# I2C.net
KiCad netlist of a schematic drawn in Altium Designer
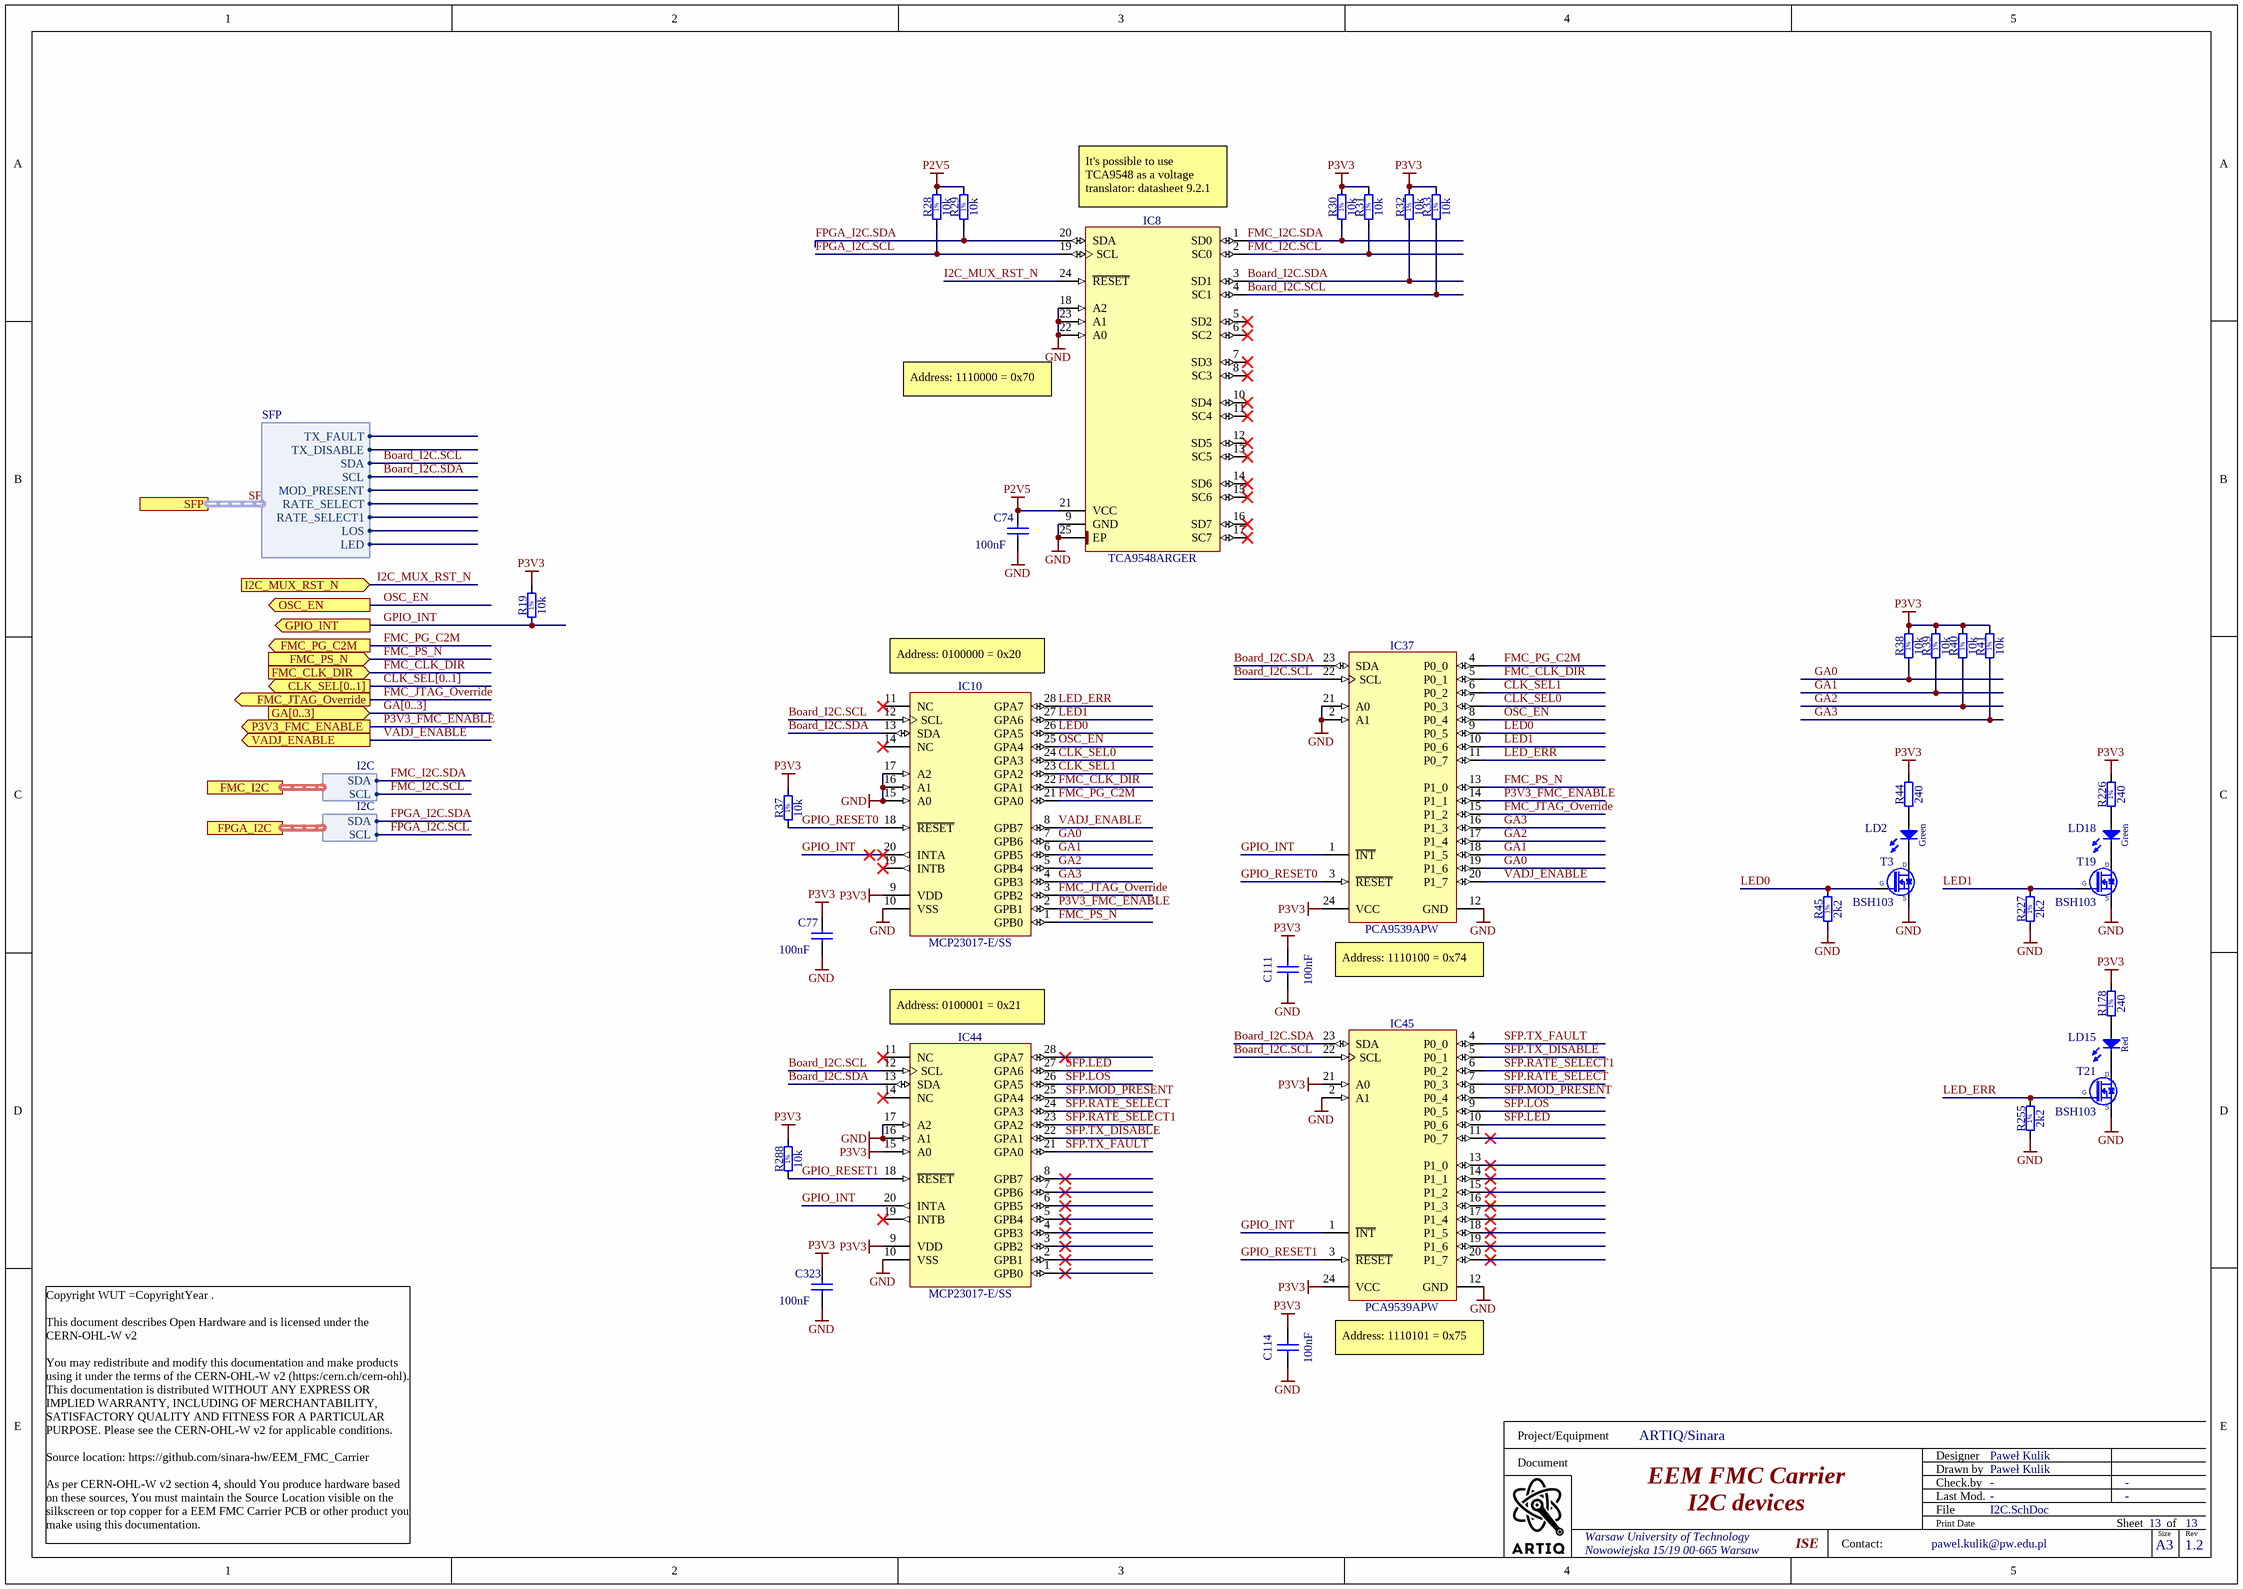
[diagram p0: I2C.SchDoc]

(export (version "E")
  (design (tool "Eeschema 10.0.6"))
  (components
    (comp (ref "C74")
      (value "100nF")
      (footprint "CAPC1005X55N")
      (description "Non-polarised capacitor")
      (fields
        (field (name "PART NUMBER") "CC0402_100NF_16V_10%_X5R")
        (field (name "VOLTAGE") "16V")
        (field (name "AUTHOR") "CERN DEM JLC")
      )
      (libsource (lib "Capacitors") (part "Capacitor - non polarized"))
    )
    (comp (ref "C77")
      (value "100nF")
      (footprint "CAPC1005X55N")
      (description "Non-polarised capacitor")
      (fields
        (field (name "PART NUMBER") "CC0402_100NF_16V_10%_X5R")
        (field (name "VOLTAGE") "16V")
        (field (name "AUTHOR") "CERN DEM JLC")
      )
      (libsource (lib "Capacitors") (part "Capacitor - non polarized"))
    )
    (comp (ref "C111")
      (value "100nF")
      (footprint "CAPC0603X33N")
      (description "Non-polarised capacitor")
      (fields
        (field (name "PART NUMBER") "CC0201_100NF_6.3V_10%_X5R")
        (field (name "VOLTAGE") "6.3V")
        (field (name "AUTHOR") "CERN DEM JLC")
      )
      (libsource (lib "Capacitors") (part "Capacitor - non polarized"))
    )
    (comp (ref "C114")
      (value "100nF")
      (footprint "CAPC0603X33N")
      (description "Non-polarised capacitor")
      (fields
        (field (name "PART NUMBER") "CC0201_100NF_6.3V_10%_X5R")
        (field (name "VOLTAGE") "6.3V")
        (field (name "AUTHOR") "CERN DEM JLC")
      )
      (libsource (lib "Capacitors") (part "Capacitor - non polarized"))
    )
    (comp (ref "C323")
      (value "100nF")
      (footprint "CAPC1005X55N")
      (description "Non-polarised capacitor")
      (fields
        (field (name "PART NUMBER") "CC0402_100NF_16V_10%_X5R")
        (field (name "VOLTAGE") "16V")
        (field (name "AUTHOR") "CERN DEM JLC")
      )
      (libsource (lib "Capacitors") (part "Capacitor - non polarized"))
    )
    (comp (ref "IC8")
      (value "TCA9548ARGER")
      (footprint "QFN50P400X400X100-25N-S220")
      (description "Low Voltage 8-Channel I2C Switch With Reset")
      (fields (field (name "MANUFACTURER") "TEXAS INSTRUMENTS") (field (name "AUTHOR") "CERN DEM JLC"))
      (libsource (lib "ICs And Semiconductors") (part "TCA9548ARGER"))
    )
    (comp (ref "IC10")
      (value "MCP23017-E/SS")
      (footprint "SOP65P780X200-28N")
      (description "16-bit I/O Port Expander With Serial Interface")
      (fields (field (name "MANUFACTURER") "MICROCHIP TECHNOLOGY") (field (name "AUTHOR") "CERN DEM JLC"))
      (libsource (lib "ICs And Semiconductors") (part "MCP23017-E/SS"))
    )
    (comp (ref "IC37")
      (value "PCA9539APW")
      (footprint "SOP65P640X110-24N")
      (description "Low-Voltage 16-Bit I2C-Bus I/O Port with Interrupt and Reset")
      (fields (field (name "MANUFACTURER") "NXP SEMICONDUCTORS") (field (name "AUTHOR") "CERN DEM JMW"))
      (libsource (lib "ICs And Semiconductors") (part "PCA9539APW"))
    )
    (comp (ref "IC44")
      (value "MCP23017-E/SS")
      (footprint "SOP65P780X200-28N")
      (description "16-bit I/O Port Expander With Serial Interface")
      (fields (field (name "MANUFACTURER") "MICROCHIP TECHNOLOGY") (field (name "AUTHOR") "CERN DEM JLC"))
      (libsource (lib "ICs And Semiconductors") (part "MCP23017-E/SS"))
    )
    (comp (ref "IC45")
      (value "PCA9539APW")
      (footprint "SOP65P640X110-24N")
      (description "Low-Voltage 16-Bit I2C-Bus I/O Port with Interrupt and Reset")
      (fields (field (name "MANUFACTURER") "NXP SEMICONDUCTORS") (field (name "AUTHOR") "CERN DEM JMW"))
      (libsource (lib "ICs And Semiconductors") (part "PCA9539APW"))
    )
    (comp (ref "LD2")
      (value "Green")
      (footprint "LED_AVAGO_HSME-C120")
      (description "LED Green 1C 2A")
      (fields
        (field (name "MANUFACTURER PART NUMBER") "HSME-C120")
        (field (name "PART NUMBER") "LED_AVAGO_HSME-C120")
        (field (name "AUTHOR") "CERN DEM JMW")
      )
      (libsource (lib "ICs And Semiconductors") (part "LED Green 1C 2A"))
    )
    (comp (ref "LD15")
      (value "Red")
      (footprint "LED_AVAGO_HSMC-C120")
      (description "LED Red 1C 2A")
      (fields
        (field (name "MANUFACTURER PART NUMBER") "HSMC-C120")
        (field (name "PART NUMBER") "LED_AVAGO_HSMC-C120")
        (field (name "AUTHOR") "CERN DEM JMW")
      )
      (libsource (lib "ICs And Semiconductors") (part "LED Red 1C 2A"))
    )
    (comp (ref "LD18")
      (value "Green")
      (footprint "LED_AVAGO_HSME-C120")
      (description "LED Green 1C 2A")
      (fields
        (field (name "MANUFACTURER PART NUMBER") "HSME-C120")
        (field (name "PART NUMBER") "LED_AVAGO_HSME-C120")
        (field (name "AUTHOR") "CERN DEM JMW")
      )
      (libsource (lib "ICs And Semiconductors") (part "LED Green 1C 2A"))
    )
    (comp (ref "R19")
      (value "10k")
      (footprint "RESC1005X40N")
      (description "Resistor - 1%")
      (fields
        (field (name "PART NUMBER") "R0402_10K_1%_0.0625W_100PPM")
        (field (name "POWER") "0.0625W")
        (field (name "AUTHOR") "CERN DEM JLC")
      )
      (libsource (lib "Resistors") (part "Resistor - 1%"))
    )
    (comp (ref "R28")
      (value "10k")
      (footprint "RESC1005X40N")
      (description "Resistor - 1%")
      (fields
        (field (name "PART NUMBER") "R0402_10K_1%_0.0625W_100PPM")
        (field (name "POWER") "0.0625W")
        (field (name "AUTHOR") "CERN DEM JLC")
      )
      (libsource (lib "Resistors") (part "Resistor - 1%"))
    )
    (comp (ref "R29")
      (value "10k")
      (footprint "RESC1005X40N")
      (description "Resistor - 1%")
      (fields
        (field (name "PART NUMBER") "R0402_10K_1%_0.0625W_100PPM")
        (field (name "POWER") "0.0625W")
        (field (name "AUTHOR") "CERN DEM JLC")
      )
      (libsource (lib "Resistors") (part "Resistor - 1%"))
    )
    (comp (ref "R30")
      (value "10k")
      (footprint "RESC1005X40N")
      (description "Resistor - 1%")
      (fields
        (field (name "PART NUMBER") "R0402_10K_1%_0.0625W_100PPM")
        (field (name "POWER") "0.0625W")
        (field (name "AUTHOR") "CERN DEM JLC")
      )
      (libsource (lib "Resistors") (part "Resistor - 1%"))
    )
    (comp (ref "R31")
      (value "10k")
      (footprint "RESC1005X40N")
      (description "Resistor - 1%")
      (fields
        (field (name "PART NUMBER") "R0402_10K_1%_0.0625W_100PPM")
        (field (name "POWER") "0.0625W")
        (field (name "AUTHOR") "CERN DEM JLC")
      )
      (libsource (lib "Resistors") (part "Resistor - 1%"))
    )
    (comp (ref "R32")
      (value "10k")
      (footprint "RESC1005X40N")
      (description "Resistor - 1%")
      (fields
        (field (name "PART NUMBER") "R0402_10K_1%_0.0625W_100PPM")
        (field (name "POWER") "0.0625W")
        (field (name "AUTHOR") "CERN DEM JLC")
      )
      (libsource (lib "Resistors") (part "Resistor - 1%"))
    )
    (comp (ref "R33")
      (value "10k")
      (footprint "RESC1005X40N")
      (description "Resistor - 1%")
      (fields
        (field (name "PART NUMBER") "R0402_10K_1%_0.0625W_100PPM")
        (field (name "POWER") "0.0625W")
        (field (name "AUTHOR") "CERN DEM JLC")
      )
      (libsource (lib "Resistors") (part "Resistor - 1%"))
    )
    (comp (ref "R37")
      (value "10k")
      (footprint "RESC1005X40N")
      (description "Resistor - 1%")
      (fields
        (field (name "PART NUMBER") "R0402_10K_1%_0.0625W_100PPM")
        (field (name "POWER") "0.0625W")
        (field (name "AUTHOR") "CERN DEM JLC")
      )
      (libsource (lib "Resistors") (part "Resistor - 1%"))
    )
    (comp (ref "R38")
      (value "10k")
      (footprint "RESC1005X40N")
      (description "Resistor - 1%")
      (fields
        (field (name "PART NUMBER") "R0402_10K_1%_0.0625W_100PPM")
        (field (name "POWER") "0.0625W")
        (field (name "AUTHOR") "CERN DEM JLC")
      )
      (libsource (lib "Resistors") (part "Resistor - 1%"))
    )
    (comp (ref "R39")
      (value "10k")
      (footprint "RESC1005X40N")
      (description "Resistor - 1%")
      (fields
        (field (name "PART NUMBER") "R0402_10K_1%_0.0625W_100PPM")
        (field (name "POWER") "0.0625W")
        (field (name "AUTHOR") "CERN DEM JLC")
      )
      (libsource (lib "Resistors") (part "Resistor - 1%"))
    )
    (comp (ref "R40")
      (value "10k")
      (footprint "RESC1005X40N")
      (description "Resistor - 1%")
      (fields
        (field (name "PART NUMBER") "R0402_10K_1%_0.0625W_100PPM")
        (field (name "POWER") "0.0625W")
        (field (name "AUTHOR") "CERN DEM JLC")
      )
      (libsource (lib "Resistors") (part "Resistor - 1%"))
    )
    (comp (ref "R41")
      (value "10k")
      (footprint "RESC1005X40N")
      (description "Resistor - 1%")
      (fields
        (field (name "PART NUMBER") "R0402_10K_1%_0.0625W_100PPM")
        (field (name "POWER") "0.0625W")
        (field (name "AUTHOR") "CERN DEM JLC")
      )
      (libsource (lib "Resistors") (part "Resistor - 1%"))
    )
    (comp (ref "R44")
      (value "240")
      (footprint "RESC1005X40N")
      (description "Resistor - 1%")
      (fields
        (field (name "PART NUMBER") "R0402_240R_1%_0.0625W_100PPM")
        (field (name "POWER") "0.0625W")
        (field (name "AUTHOR") "CERN DEM JLC")
      )
      (libsource (lib "Resistors") (part "Resistor - 1%"))
    )
    (comp (ref "R45")
      (value "2k2")
      (footprint "RESC1005X40N")
      (description "Resistor - 1%")
      (fields
        (field (name "PART NUMBER") "R0402_2K2_1%_0.0625W_100PPM")
        (field (name "POWER") "0.0625W")
        (field (name "AUTHOR") "CERN DEM JLC")
      )
      (libsource (lib "Resistors") (part "Resistor - 1%"))
    )
    (comp (ref "R178")
      (value "240")
      (footprint "RESC1005X40N")
      (description "Resistor - 1%")
      (fields
        (field (name "PART NUMBER") "R0402_240R_1%_0.0625W_100PPM")
        (field (name "POWER") "0.0625W")
        (field (name "AUTHOR") "CERN DEM JLC")
      )
      (libsource (lib "Resistors") (part "Resistor - 1%"))
    )
    (comp (ref "R226")
      (value "240")
      (footprint "RESC1005X40N")
      (description "Resistor - 1%")
      (fields
        (field (name "PART NUMBER") "R0402_240R_1%_0.0625W_100PPM")
        (field (name "POWER") "0.0625W")
        (field (name "AUTHOR") "CERN DEM JLC")
      )
      (libsource (lib "Resistors") (part "Resistor - 1%"))
    )
    (comp (ref "R227")
      (value "2k2")
      (footprint "RESC1005X40N")
      (description "Resistor - 1%")
      (fields
        (field (name "PART NUMBER") "R0402_2K2_1%_0.0625W_100PPM")
        (field (name "POWER") "0.0625W")
        (field (name "AUTHOR") "CERN DEM JLC")
      )
      (libsource (lib "Resistors") (part "Resistor - 1%"))
    )
    (comp (ref "R255")
      (value "2k2")
      (footprint "RESC1005X40N")
      (description "Resistor - 1%")
      (fields
        (field (name "PART NUMBER") "R0402_2K2_1%_0.0625W_100PPM")
        (field (name "POWER") "0.0625W")
        (field (name "AUTHOR") "CERN DEM JLC")
      )
      (libsource (lib "Resistors") (part "Resistor - 1%"))
    )
    (comp (ref "R288")
      (value "10k")
      (footprint "RESC1005X40N")
      (description "Resistor - 1%")
      (fields
        (field (name "PART NUMBER") "R0402_10K_1%_0.0625W_100PPM")
        (field (name "POWER") "0.0625W")
        (field (name "AUTHOR") "CERN DEM JLC")
      )
      (libsource (lib "Resistors") (part "Resistor - 1%"))
    )
    (comp (ref "T3")
      (value "BSH103")
      (footprint "SOT95P230X110-3N")
      (description "N-CHANNEL MOSFET WITH DIODE")
      (fields (field (name "MANUFACTURER") "NEXPERIA") (field (name "AUTHOR") "CERN DEM JLC"))
      (libsource (lib "ICs And Semiconductors") (part "N-MOSFET-D 1G 2S 3D"))
    )
    (comp (ref "T19")
      (value "BSH103")
      (footprint "SOT95P230X110-3N")
      (description "N-CHANNEL MOSFET WITH DIODE")
      (fields (field (name "MANUFACTURER") "NEXPERIA") (field (name "AUTHOR") "CERN DEM JLC"))
      (libsource (lib "ICs And Semiconductors") (part "N-MOSFET-D 1G 2S 3D"))
    )
    (comp (ref "T21")
      (value "BSH103")
      (footprint "SOT95P230X110-3N")
      (description "N-CHANNEL MOSFET WITH DIODE")
      (fields (field (name "MANUFACTURER") "NEXPERIA") (field (name "AUTHOR") "CERN DEM JLC"))
      (libsource (lib "ICs And Semiconductors") (part "N-MOSFET-D 1G 2S 3D"))
    )
  )
  (nets
    (net (code "3") (name "/Board_I2C.SCL") (class "Default")
      (node (ref "IC10") (pin "12") (pinfunction "SCL_12") (pintype "input"))
      (node (ref "IC37") (pin "22") (pinfunction "SCL_22") (pintype "input"))
      (node (ref "IC44") (pin "12") (pinfunction "SCL_12") (pintype "input"))
      (node (ref "IC45") (pin "22") (pinfunction "SCL_22") (pintype "input"))
      (node (ref "IC8") (pin "4") (pinfunction "SC1_4") (pintype "bidirectional"))
      (node (ref "R33") (pin "1") (pinfunction "1_1") (pintype "passive"))
    )
    (net (code "4") (name "/Board_I2C.SDA") (class "Default")
      (node (ref "IC10") (pin "13") (pinfunction "SDA_13") (pintype "bidirectional"))
      (node (ref "IC37") (pin "23") (pinfunction "SDA_23") (pintype "bidirectional"))
      (node (ref "IC44") (pin "13") (pinfunction "SDA_13") (pintype "bidirectional"))
      (node (ref "IC45") (pin "23") (pinfunction "SDA_23") (pintype "bidirectional"))
      (node (ref "IC8") (pin "3") (pinfunction "SD1_3") (pintype "bidirectional"))
      (node (ref "R32") (pin "1") (pinfunction "1_1") (pintype "passive"))
    )
    (net (code "5") (name "/CLK_SEL0") (class "Default")
      (node (ref "IC10") (pin "24") (pinfunction "GPA3_24") (pintype "bidirectional"))
      (node (ref "IC37") (pin "7") (pinfunction "P0_3_7") (pintype "bidirectional"))
    )
    (net (code "6") (name "/CLK_SEL1") (class "Default")
      (node (ref "IC10") (pin "23") (pinfunction "GPA2_23") (pintype "bidirectional"))
      (node (ref "IC37") (pin "6") (pinfunction "P0_2_6") (pintype "bidirectional"))
    )
    (net (code "8") (name "/FMC_CLK_DIR") (class "Default")
      (node (ref "IC10") (pin "22") (pinfunction "GPA1_22") (pintype "bidirectional"))
      (node (ref "IC37") (pin "5") (pinfunction "P0_1_5") (pintype "bidirectional"))
    )
    (net (code "9") (name "/FMC_I2C.SCL") (class "Default")
      (node (ref "IC8") (pin "2") (pinfunction "SC0_2") (pintype "bidirectional"))
      (node (ref "R31") (pin "1") (pinfunction "1_1") (pintype "passive"))
    )
    (net (code "10") (name "/FMC_I2C.SDA") (class "Default")
      (node (ref "IC8") (pin "1") (pinfunction "SD0_1") (pintype "bidirectional"))
      (node (ref "R30") (pin "1") (pinfunction "1_1") (pintype "passive"))
    )
    (net (code "11") (name "/FMC_JTAG_Override") (class "Default")
      (node (ref "IC10") (pin "3") (pinfunction "GPB2_3") (pintype "bidirectional"))
      (node (ref "IC37") (pin "15") (pinfunction "P1_2_15") (pintype "bidirectional"))
    )
    (net (code "12") (name "/FMC_PG_C2M") (class "Default")
      (node (ref "IC10") (pin "21") (pinfunction "GPA0_21") (pintype "bidirectional"))
      (node (ref "IC37") (pin "4") (pinfunction "P0_0_4") (pintype "bidirectional"))
    )
    (net (code "13") (name "/FMC_PS_N") (class "Default")
      (node (ref "IC10") (pin "1") (pinfunction "GPB0_1") (pintype "bidirectional"))
      (node (ref "IC37") (pin "13") (pinfunction "P1_0_13") (pintype "bidirectional"))
    )
    (net (code "14") (name "/FPGA_I2C.SCL") (class "Default")
      (node (ref "IC8") (pin "19") (pinfunction "SCL_19") (pintype "bidirectional"))
      (node (ref "R28") (pin "1") (pinfunction "1_1") (pintype "passive"))
    )
    (net (code "15") (name "/FPGA_I2C.SDA") (class "Default")
      (node (ref "IC8") (pin "20") (pinfunction "SDA_20") (pintype "bidirectional"))
      (node (ref "R29") (pin "1") (pinfunction "1_1") (pintype "passive"))
    )
    (net (code "16") (name "/GA0") (class "Default")
      (node (ref "IC10") (pin "7") (pinfunction "GPB6_7") (pintype "bidirectional"))
      (node (ref "IC37") (pin "19") (pinfunction "P1_6_19") (pintype "bidirectional"))
      (node (ref "R38") (pin "1") (pinfunction "1_1") (pintype "passive"))
    )
    (net (code "17") (name "/GA1") (class "Default")
      (node (ref "IC10") (pin "6") (pinfunction "GPB5_6") (pintype "bidirectional"))
      (node (ref "IC37") (pin "18") (pinfunction "P1_5_18") (pintype "bidirectional"))
      (node (ref "R39") (pin "1") (pinfunction "1_1") (pintype "passive"))
    )
    (net (code "18") (name "/GA2") (class "Default")
      (node (ref "IC10") (pin "5") (pinfunction "GPB4_5") (pintype "bidirectional"))
      (node (ref "IC37") (pin "17") (pinfunction "P1_4_17") (pintype "bidirectional"))
      (node (ref "R40") (pin "1") (pinfunction "1_1") (pintype "passive"))
    )
    (net (code "19") (name "/GA3") (class "Default")
      (node (ref "IC10") (pin "4") (pinfunction "GPB3_4") (pintype "bidirectional"))
      (node (ref "IC37") (pin "16") (pinfunction "P1_3_16") (pintype "bidirectional"))
      (node (ref "R41") (pin "1") (pinfunction "1_1") (pintype "passive"))
    )
    (net (code "21") (name "/GPIO_INT") (class "Default")
      (node (ref "IC10") (pin "20") (pinfunction "INTA_20") (pintype "output"))
      (node (ref "IC37") (pin "1") (pinfunction "~{INT}_1") (pintype "open_collector"))
      (node (ref "IC44") (pin "20") (pinfunction "INTA_20") (pintype "output"))
      (node (ref "IC45") (pin "1") (pinfunction "~{INT}_1") (pintype "open_collector"))
      (node (ref "R19") (pin "1") (pinfunction "1_1") (pintype "passive"))
    )
    (net (code "22") (name "/GPIO_RESET0") (class "Default")
      (node (ref "IC10") (pin "18") (pinfunction "~{RESET}_18") (pintype "input"))
      (node (ref "IC37") (pin "3") (pinfunction "~{RESET}_3") (pintype "input"))
      (node (ref "R37") (pin "1") (pinfunction "1_1") (pintype "passive"))
    )
    (net (code "23") (name "/GPIO_RESET1") (class "Default")
      (node (ref "IC44") (pin "18") (pinfunction "~{RESET}_18") (pintype "input"))
      (node (ref "IC45") (pin "3") (pinfunction "~{RESET}_3") (pintype "input"))
      (node (ref "R288") (pin "1") (pinfunction "1_1") (pintype "passive"))
    )
    (net (code "24") (name "/I2C_MUX_RST_N") (class "Default")
      (node (ref "IC8") (pin "24") (pinfunction "~{RESET}_24") (pintype "input"))
    )
    (net (code "25") (name "/LED0") (class "Default")
      (node (ref "IC10") (pin "26") (pinfunction "GPA5_26") (pintype "bidirectional"))
      (node (ref "IC37") (pin "9") (pinfunction "P0_5_9") (pintype "bidirectional"))
      (node (ref "R45") (pin "2") (pinfunction "2_2") (pintype "passive"))
      (node (ref "T3") (pin "1") (pinfunction "G_1") (pintype "passive"))
    )
    (net (code "26") (name "/LED1") (class "Default")
      (node (ref "IC10") (pin "27") (pinfunction "GPA6_27") (pintype "bidirectional"))
      (node (ref "IC37") (pin "10") (pinfunction "P0_6_10") (pintype "bidirectional"))
      (node (ref "R227") (pin "2") (pinfunction "2_2") (pintype "passive"))
      (node (ref "T19") (pin "1") (pinfunction "G_1") (pintype "passive"))
    )
    (net (code "27") (name "/LED_ERR") (class "Default")
      (node (ref "IC10") (pin "28") (pinfunction "GPA7_28") (pintype "bidirectional"))
      (node (ref "IC37") (pin "11") (pinfunction "P0_7_11") (pintype "bidirectional"))
      (node (ref "R255") (pin "2") (pinfunction "2_2") (pintype "passive"))
      (node (ref "T21") (pin "1") (pinfunction "G_1") (pintype "passive"))
    )
    (net (code "28") (name "/OSC_EN") (class "Default")
      (node (ref "IC10") (pin "25") (pinfunction "GPA4_25") (pintype "bidirectional"))
      (node (ref "IC37") (pin "8") (pinfunction "P0_4_8") (pintype "bidirectional"))
    )
    (net (code "29") (name "/P3V3_FMC_ENABLE") (class "Default")
      (node (ref "IC10") (pin "2") (pinfunction "GPB1_2") (pintype "bidirectional"))
      (node (ref "IC37") (pin "14") (pinfunction "P1_1_14") (pintype "bidirectional"))
    )
    (net (code "30") (name "/SFP.LED") (class "Default")
      (node (ref "IC44") (pin "27") (pinfunction "GPA6_27") (pintype "bidirectional"))
      (node (ref "IC45") (pin "10") (pinfunction "P0_6_10") (pintype "bidirectional"))
    )
    (net (code "31") (name "/SFP.LOS") (class "Default")
      (node (ref "IC44") (pin "26") (pinfunction "GPA5_26") (pintype "bidirectional"))
      (node (ref "IC45") (pin "9") (pinfunction "P0_5_9") (pintype "bidirectional"))
    )
    (net (code "32") (name "/SFP.MOD_PRESENT") (class "Default")
      (node (ref "IC44") (pin "25") (pinfunction "GPA4_25") (pintype "bidirectional"))
      (node (ref "IC45") (pin "8") (pinfunction "P0_4_8") (pintype "bidirectional"))
    )
    (net (code "33") (name "/SFP.RATE_SELECT") (class "Default")
      (node (ref "IC44") (pin "24") (pinfunction "GPA3_24") (pintype "bidirectional"))
      (node (ref "IC45") (pin "7") (pinfunction "P0_3_7") (pintype "bidirectional"))
    )
    (net (code "34") (name "/SFP.RATE_SELECT1") (class "Default")
      (node (ref "IC44") (pin "23") (pinfunction "GPA2_23") (pintype "bidirectional"))
      (node (ref "IC45") (pin "6") (pinfunction "P0_2_6") (pintype "bidirectional"))
    )
    (net (code "35") (name "/SFP.TX_DISABLE") (class "Default")
      (node (ref "IC44") (pin "22") (pinfunction "GPA1_22") (pintype "bidirectional"))
      (node (ref "IC45") (pin "5") (pinfunction "P0_1_5") (pintype "bidirectional"))
    )
    (net (code "36") (name "/SFP.TX_FAULT") (class "Default")
      (node (ref "IC44") (pin "21") (pinfunction "GPA0_21") (pintype "bidirectional"))
      (node (ref "IC45") (pin "4") (pinfunction "P0_0_4") (pintype "bidirectional"))
    )
    (net (code "38") (name "/VADJ_ENABLE") (class "Default")
      (node (ref "IC10") (pin "8") (pinfunction "GPB7_8") (pintype "bidirectional"))
      (node (ref "IC37") (pin "20") (pinfunction "P1_7_20") (pintype "bidirectional"))
    )
    (net (code "40") (name "GND") (class "Default")
      (node (ref "C111") (pin "1") (pinfunction "1_1") (pintype "passive"))
      (node (ref "C114") (pin "1") (pinfunction "1_1") (pintype "passive"))
      (node (ref "C323") (pin "1") (pinfunction "1_1") (pintype "passive"))
      (node (ref "C74") (pin "1") (pinfunction "1_1") (pintype "passive"))
      (node (ref "C77") (pin "1") (pinfunction "1_1") (pintype "passive"))
      (node (ref "IC10") (pin "10") (pinfunction "VSS_10") (pintype "power_in"))
      (node (ref "IC10") (pin "15") (pinfunction "A0_15") (pintype "input"))
      (node (ref "IC10") (pin "16") (pinfunction "A1_16") (pintype "input"))
      (node (ref "IC10") (pin "17") (pinfunction "A2_17") (pintype "input"))
      (node (ref "IC37") (pin "12") (pinfunction "GND_12") (pintype "power_in"))
      (node (ref "IC37") (pin "2") (pinfunction "A1_2") (pintype "input"))
      (node (ref "IC37") (pin "21") (pinfunction "A0_21") (pintype "input"))
      (node (ref "IC44") (pin "10") (pinfunction "VSS_10") (pintype "power_in"))
      (node (ref "IC44") (pin "16") (pinfunction "A1_16") (pintype "input"))
      (node (ref "IC44") (pin "17") (pinfunction "A2_17") (pintype "input"))
      (node (ref "IC45") (pin "12") (pinfunction "GND_12") (pintype "power_in"))
      (node (ref "IC45") (pin "2") (pinfunction "A1_2") (pintype "input"))
      (node (ref "IC8") (pin "18") (pinfunction "A2_18") (pintype "input"))
      (node (ref "IC8") (pin "22") (pinfunction "A0_22") (pintype "input"))
      (node (ref "IC8") (pin "23") (pinfunction "A1_23") (pintype "input"))
      (node (ref "IC8") (pin "25") (pinfunction "EP_25") (pintype "power_in"))
      (node (ref "IC8") (pin "9") (pinfunction "GND_9") (pintype "power_in"))
      (node (ref "R227") (pin "1") (pinfunction "1_1") (pintype "passive"))
      (node (ref "R255") (pin "1") (pinfunction "1_1") (pintype "passive"))
      (node (ref "R45") (pin "1") (pinfunction "1_1") (pintype "passive"))
      (node (ref "T19") (pin "2") (pinfunction "S_2") (pintype "passive"))
      (node (ref "T21") (pin "2") (pinfunction "S_2") (pintype "passive"))
      (node (ref "T3") (pin "2") (pinfunction "S_2") (pintype "passive"))
    )
    (net (code "41") (name "Net-(LD2-A)") (class "Default")
      (node (ref "LD2") (pin "2") (pinfunction "A_2") (pintype "passive"))
      (node (ref "R44") (pin "1") (pinfunction "1_1") (pintype "passive"))
    )
    (net (code "42") (name "Net-(LD2-C)") (class "Default")
      (node (ref "LD2") (pin "1") (pinfunction "C_1") (pintype "passive"))
      (node (ref "T3") (pin "3") (pinfunction "D_3") (pintype "passive"))
    )
    (net (code "43") (name "Net-(LD15-A)") (class "Default")
      (node (ref "LD15") (pin "2") (pinfunction "A_2") (pintype "passive"))
      (node (ref "R178") (pin "1") (pinfunction "1_1") (pintype "passive"))
    )
    (net (code "44") (name "Net-(LD15-C)") (class "Default")
      (node (ref "LD15") (pin "1") (pinfunction "C_1") (pintype "passive"))
      (node (ref "T21") (pin "3") (pinfunction "D_3") (pintype "passive"))
    )
    (net (code "45") (name "Net-(LD18-A)") (class "Default")
      (node (ref "LD18") (pin "2") (pinfunction "A_2") (pintype "passive"))
      (node (ref "R226") (pin "1") (pinfunction "1_1") (pintype "passive"))
    )
    (net (code "46") (name "Net-(LD18-C)") (class "Default")
      (node (ref "LD18") (pin "1") (pinfunction "C_1") (pintype "passive"))
      (node (ref "T19") (pin "3") (pinfunction "D_3") (pintype "passive"))
    )
    (net (code "47") (name "P2V5") (class "Default")
      (node (ref "C74") (pin "2") (pinfunction "2_2") (pintype "passive"))
      (node (ref "IC8") (pin "21") (pinfunction "VCC_21") (pintype "power_in"))
      (node (ref "R28") (pin "2") (pinfunction "2_2") (pintype "passive"))
      (node (ref "R29") (pin "2") (pinfunction "2_2") (pintype "passive"))
    )
    (net (code "48") (name "P3V3") (class "Default")
      (node (ref "C111") (pin "2") (pinfunction "2_2") (pintype "passive"))
      (node (ref "C114") (pin "2") (pinfunction "2_2") (pintype "passive"))
      (node (ref "C323") (pin "2") (pinfunction "2_2") (pintype "passive"))
      (node (ref "C77") (pin "2") (pinfunction "2_2") (pintype "passive"))
      (node (ref "IC10") (pin "9") (pinfunction "VDD_9") (pintype "power_in"))
      (node (ref "IC37") (pin "24") (pinfunction "VCC_24") (pintype "power_in"))
      (node (ref "IC44") (pin "15") (pinfunction "A0_15") (pintype "input"))
      (node (ref "IC44") (pin "9") (pinfunction "VDD_9") (pintype "power_in"))
      (node (ref "IC45") (pin "21") (pinfunction "A0_21") (pintype "input"))
      (node (ref "IC45") (pin "24") (pinfunction "VCC_24") (pintype "power_in"))
      (node (ref "R178") (pin "2") (pinfunction "2_2") (pintype "passive"))
      (node (ref "R19") (pin "2") (pinfunction "2_2") (pintype "passive"))
      (node (ref "R226") (pin "2") (pinfunction "2_2") (pintype "passive"))
      (node (ref "R288") (pin "2") (pinfunction "2_2") (pintype "passive"))
      (node (ref "R30") (pin "2") (pinfunction "2_2") (pintype "passive"))
      (node (ref "R31") (pin "2") (pinfunction "2_2") (pintype "passive"))
      (node (ref "R32") (pin "2") (pinfunction "2_2") (pintype "passive"))
      (node (ref "R33") (pin "2") (pinfunction "2_2") (pintype "passive"))
      (node (ref "R37") (pin "2") (pinfunction "2_2") (pintype "passive"))
      (node (ref "R38") (pin "2") (pinfunction "2_2") (pintype "passive"))
      (node (ref "R39") (pin "2") (pinfunction "2_2") (pintype "passive"))
      (node (ref "R40") (pin "2") (pinfunction "2_2") (pintype "passive"))
      (node (ref "R41") (pin "2") (pinfunction "2_2") (pintype "passive"))
      (node (ref "R44") (pin "2") (pinfunction "2_2") (pintype "passive"))
    )
    (net (code "49") (name "unconnected-(IC8-SC2-Pad6)") (class "Default")
      (node (ref "IC8") (pin "6") (pinfunction "SC2_6") (pintype "bidirectional+no_connect"))
    )
    (net (code "50") (name "unconnected-(IC8-SC3-Pad8)") (class "Default")
      (node (ref "IC8") (pin "8") (pinfunction "SC3_8") (pintype "bidirectional+no_connect"))
    )
    (net (code "51") (name "unconnected-(IC8-SC4-Pad11)") (class "Default")
      (node (ref "IC8") (pin "11") (pinfunction "SC4_11") (pintype "bidirectional+no_connect"))
    )
    (net (code "52") (name "unconnected-(IC8-SC5-Pad13)") (class "Default")
      (node (ref "IC8") (pin "13") (pinfunction "SC5_13") (pintype "bidirectional+no_connect"))
    )
    (net (code "53") (name "unconnected-(IC8-SC6-Pad15)") (class "Default")
      (node (ref "IC8") (pin "15") (pinfunction "SC6_15") (pintype "bidirectional+no_connect"))
    )
    (net (code "54") (name "unconnected-(IC8-SC7-Pad17)") (class "Default")
      (node (ref "IC8") (pin "17") (pinfunction "SC7_17") (pintype "bidirectional+no_connect"))
    )
    (net (code "55") (name "unconnected-(IC8-SD2-Pad5)") (class "Default")
      (node (ref "IC8") (pin "5") (pinfunction "SD2_5") (pintype "bidirectional+no_connect"))
    )
    (net (code "56") (name "unconnected-(IC8-SD3-Pad7)") (class "Default")
      (node (ref "IC8") (pin "7") (pinfunction "SD3_7") (pintype "bidirectional+no_connect"))
    )
    (net (code "57") (name "unconnected-(IC8-SD4-Pad10)") (class "Default")
      (node (ref "IC8") (pin "10") (pinfunction "SD4_10") (pintype "bidirectional+no_connect"))
    )
    (net (code "58") (name "unconnected-(IC8-SD5-Pad12)") (class "Default")
      (node (ref "IC8") (pin "12") (pinfunction "SD5_12") (pintype "bidirectional+no_connect"))
    )
    (net (code "59") (name "unconnected-(IC8-SD6-Pad14)") (class "Default")
      (node (ref "IC8") (pin "14") (pinfunction "SD6_14") (pintype "bidirectional+no_connect"))
    )
    (net (code "60") (name "unconnected-(IC8-SD7-Pad16)") (class "Default")
      (node (ref "IC8") (pin "16") (pinfunction "SD7_16") (pintype "bidirectional+no_connect"))
    )
    (net (code "61") (name "unconnected-(IC10-INTB-Pad19)") (class "Default")
      (node (ref "IC10") (pin "19") (pinfunction "INTB_19") (pintype "output+no_connect"))
    )
    (net (code "62") (name "unconnected-(IC10-NC-Pad11)") (class "Default")
      (node (ref "IC10") (pin "11") (pinfunction "NC_11") (pintype "passive+no_connect"))
    )
    (net (code "63") (name "unconnected-(IC10-NC-Pad14)") (class "Default")
      (node (ref "IC10") (pin "14") (pinfunction "NC_14") (pintype "passive+no_connect"))
    )
    (net (code "64") (name "unconnected-(IC44-GPA7-Pad28)") (class "Default")
      (node (ref "IC44") (pin "28") (pinfunction "GPA7_28") (pintype "bidirectional"))
    )
    (net (code "65") (name "unconnected-(IC44-GPB0-Pad1)") (class "Default")
      (node (ref "IC44") (pin "1") (pinfunction "GPB0_1") (pintype "bidirectional"))
    )
    (net (code "66") (name "unconnected-(IC44-GPB1-Pad2)") (class "Default")
      (node (ref "IC44") (pin "2") (pinfunction "GPB1_2") (pintype "bidirectional"))
    )
    (net (code "67") (name "unconnected-(IC44-GPB2-Pad3)") (class "Default")
      (node (ref "IC44") (pin "3") (pinfunction "GPB2_3") (pintype "bidirectional"))
    )
    (net (code "68") (name "unconnected-(IC44-GPB3-Pad4)") (class "Default")
      (node (ref "IC44") (pin "4") (pinfunction "GPB3_4") (pintype "bidirectional"))
    )
    (net (code "69") (name "unconnected-(IC44-GPB4-Pad5)") (class "Default")
      (node (ref "IC44") (pin "5") (pinfunction "GPB4_5") (pintype "bidirectional"))
    )
    (net (code "70") (name "unconnected-(IC44-GPB5-Pad6)") (class "Default")
      (node (ref "IC44") (pin "6") (pinfunction "GPB5_6") (pintype "bidirectional"))
    )
    (net (code "71") (name "unconnected-(IC44-GPB6-Pad7)") (class "Default")
      (node (ref "IC44") (pin "7") (pinfunction "GPB6_7") (pintype "bidirectional"))
    )
    (net (code "72") (name "unconnected-(IC44-GPB7-Pad8)") (class "Default")
      (node (ref "IC44") (pin "8") (pinfunction "GPB7_8") (pintype "bidirectional"))
    )
    (net (code "73") (name "unconnected-(IC44-INTB-Pad19)") (class "Default")
      (node (ref "IC44") (pin "19") (pinfunction "INTB_19") (pintype "output+no_connect"))
    )
    (net (code "74") (name "unconnected-(IC44-NC-Pad11)") (class "Default")
      (node (ref "IC44") (pin "11") (pinfunction "NC_11") (pintype "passive+no_connect"))
    )
    (net (code "75") (name "unconnected-(IC44-NC-Pad14)") (class "Default")
      (node (ref "IC44") (pin "14") (pinfunction "NC_14") (pintype "passive+no_connect"))
    )
    (net (code "76") (name "unconnected-(IC45-P0_7-Pad11)") (class "Default")
      (node (ref "IC45") (pin "11") (pinfunction "P0_7_11") (pintype "bidirectional"))
    )
    (net (code "77") (name "unconnected-(IC45-P1_0-Pad13)") (class "Default")
      (node (ref "IC45") (pin "13") (pinfunction "P1_0_13") (pintype "bidirectional"))
    )
    (net (code "78") (name "unconnected-(IC45-P1_1-Pad14)") (class "Default")
      (node (ref "IC45") (pin "14") (pinfunction "P1_1_14") (pintype "bidirectional"))
    )
    (net (code "79") (name "unconnected-(IC45-P1_2-Pad15)") (class "Default")
      (node (ref "IC45") (pin "15") (pinfunction "P1_2_15") (pintype "bidirectional"))
    )
    (net (code "80") (name "unconnected-(IC45-P1_3-Pad16)") (class "Default")
      (node (ref "IC45") (pin "16") (pinfunction "P1_3_16") (pintype "bidirectional"))
    )
    (net (code "81") (name "unconnected-(IC45-P1_4-Pad17)") (class "Default")
      (node (ref "IC45") (pin "17") (pinfunction "P1_4_17") (pintype "bidirectional"))
    )
    (net (code "82") (name "unconnected-(IC45-P1_5-Pad18)") (class "Default")
      (node (ref "IC45") (pin "18") (pinfunction "P1_5_18") (pintype "bidirectional"))
    )
    (net (code "83") (name "unconnected-(IC45-P1_6-Pad19)") (class "Default")
      (node (ref "IC45") (pin "19") (pinfunction "P1_6_19") (pintype "bidirectional"))
    )
    (net (code "84") (name "unconnected-(IC45-P1_7-Pad20)") (class "Default")
      (node (ref "IC45") (pin "20") (pinfunction "P1_7_20") (pintype "bidirectional"))
    )
  )
)
